# 5_ButtonsAndLeds.net
KiCad netlist of a schematic drawn in Altium Designer
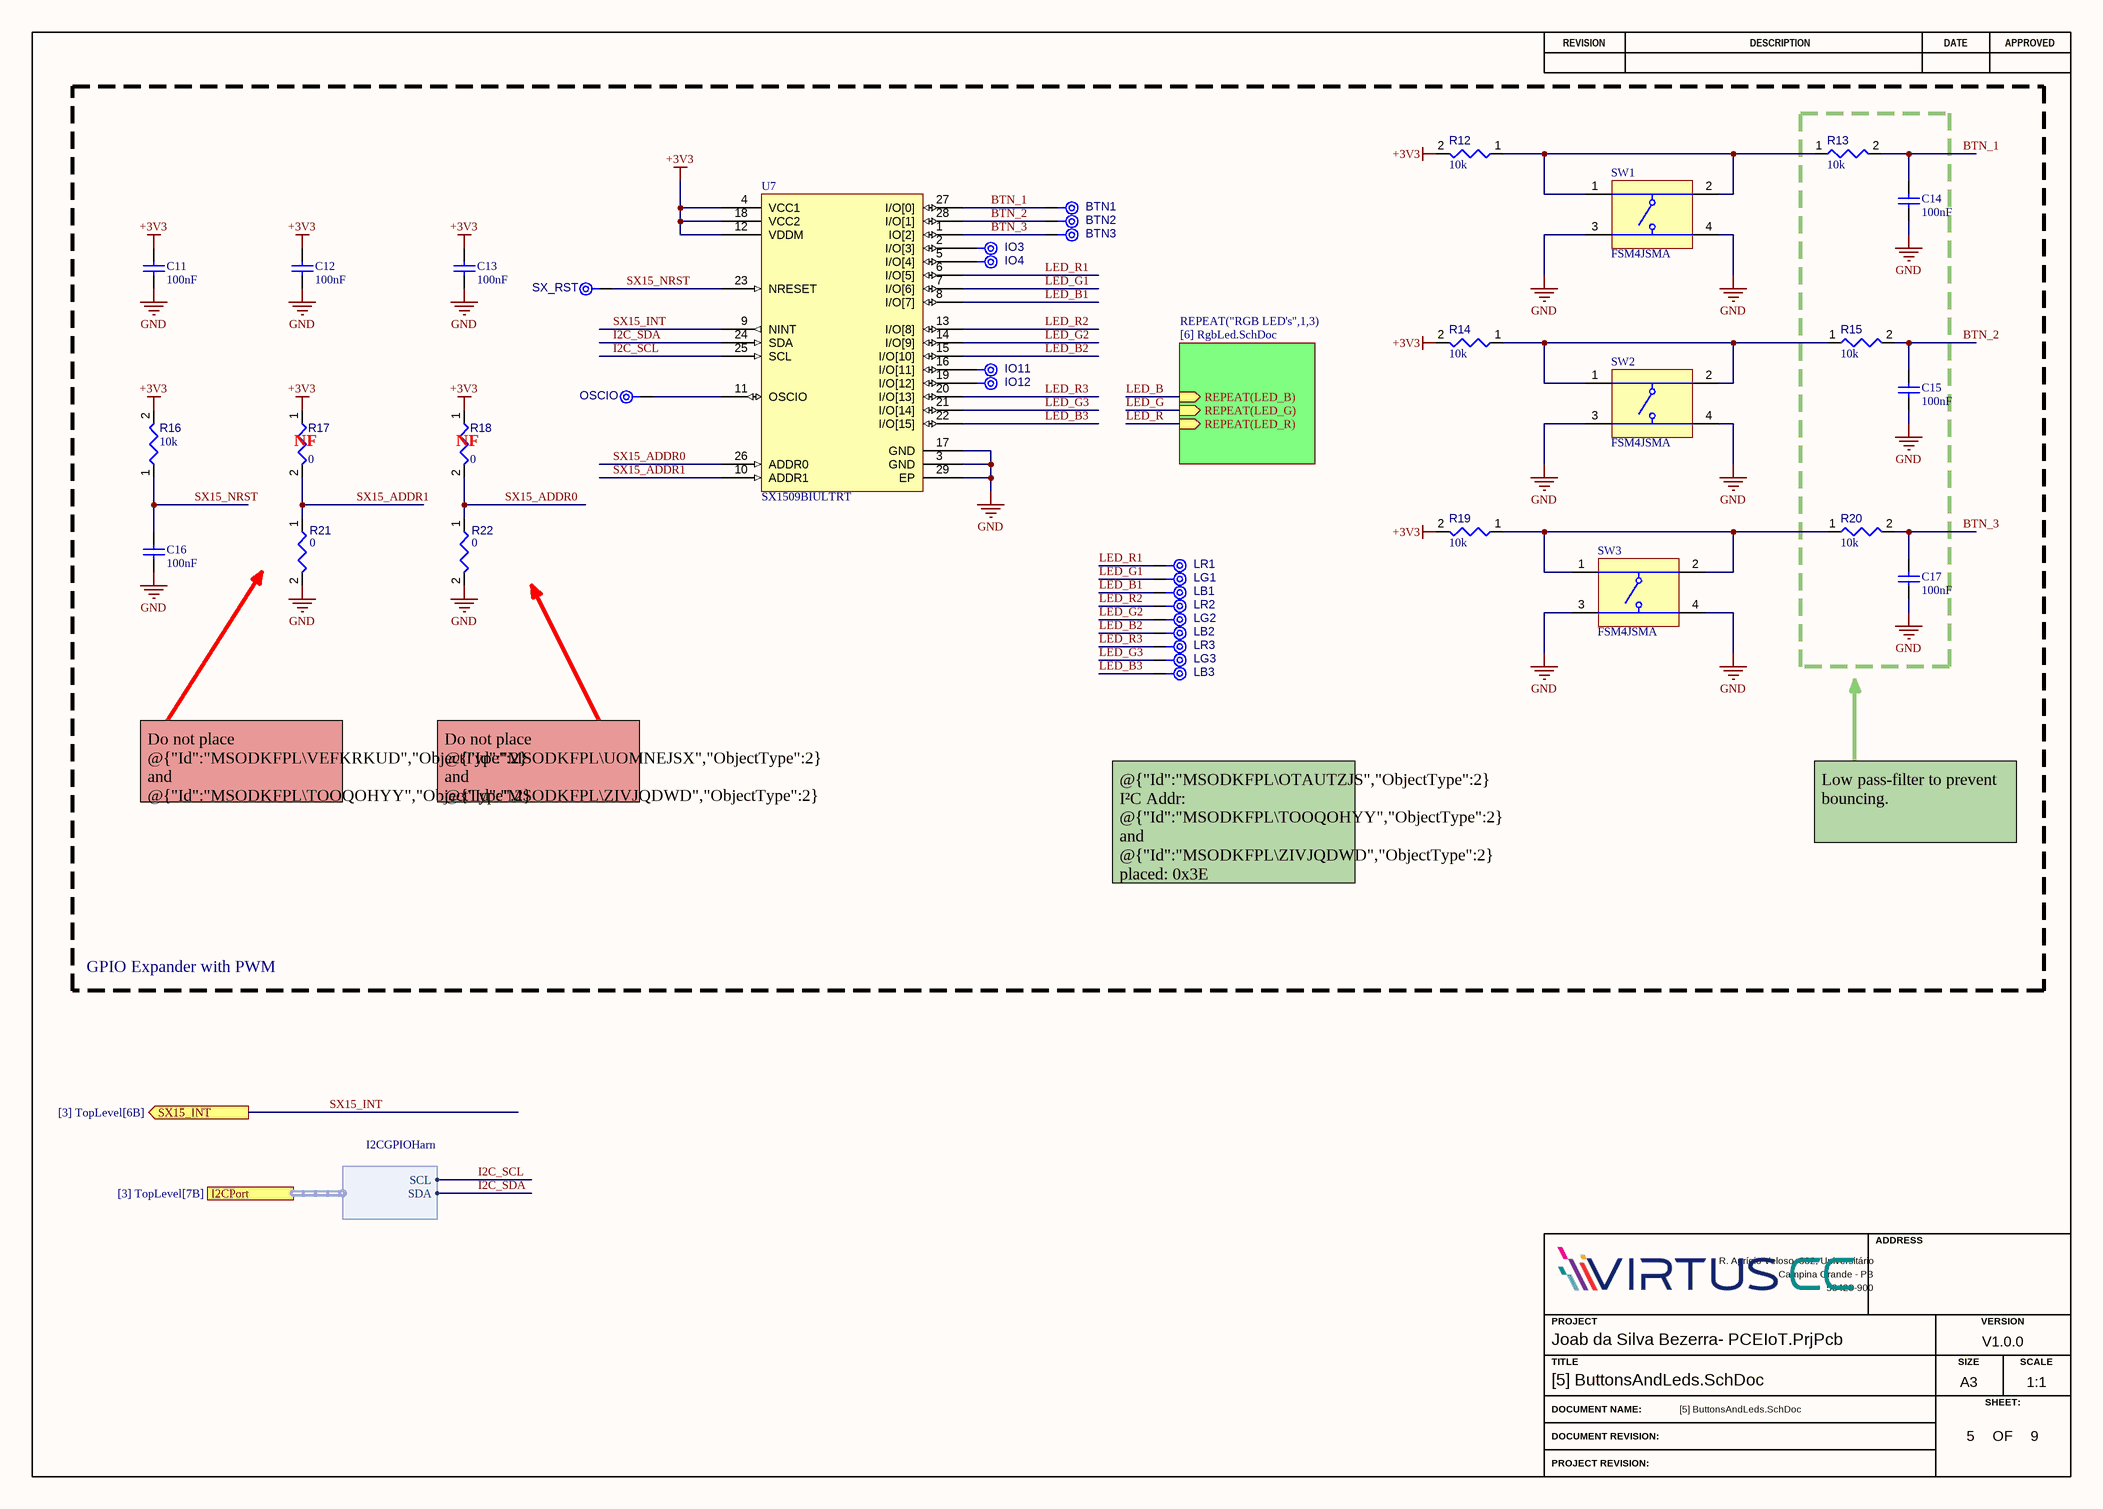
[diagram p0: [5] ButtonsAndLeds.SchDoc]

(export (version "E")
  (design (tool "Eeschema 10.0.6"))
  (components
    (comp (ref "BTN1")
      (value "TPAD6R")
      (footprint "TP06R")
      (description "0.6mm round")
      (libsource (lib "UFCG - Universidade Federal de Campina Grande") (part "CMP-001-0001-4"))
    )
    (comp (ref "BTN2")
      (value "TPAD6R")
      (footprint "TP06R")
      (description "0.6mm round")
      (libsource (lib "UFCG - Universidade Federal de Campina Grande") (part "CMP-001-0001-4"))
    )
    (comp (ref "BTN3")
      (value "TPAD6R")
      (footprint "TP06R")
      (description "0.6mm round")
      (libsource (lib "UFCG - Universidade Federal de Campina Grande") (part "CMP-001-0001-4"))
    )
    (comp (ref "C11")
      (value "100nF")
      (footprint "CAPC0603(1608)100_L")
      (description "Multilayer Ceramic Capacitor, 0.1 uF, 16 V, ± 20%, X7R, 0603 [1608 Metric]")
      (fields (field (name "TOLERANCE") "20%") (field (name "Comment") "VJ0603Y104MXJCW1BC"))
      (libsource (lib "UFCG - Universidade Federal de Campina Grande") (part "CAP"))
    )
    (comp (ref "C12")
      (value "100nF")
      (footprint "CAPC0603(1608)100_L")
      (description "Multilayer Ceramic Capacitor, 0.1 uF, 16 V, ± 20%, X7R, 0603 [1608 Metric]")
      (fields (field (name "TOLERANCE") "20%") (field (name "Comment") "VJ0603Y104MXJCW1BC"))
      (libsource (lib "UFCG - Universidade Federal de Campina Grande") (part "CAP"))
    )
    (comp (ref "C13")
      (value "100nF")
      (footprint "CAPC0603(1608)100_L")
      (description "Multilayer Ceramic Capacitor, 0.1 uF, 16 V, ± 20%, X7R, 0603 [1608 Metric]")
      (fields (field (name "TOLERANCE") "20%") (field (name "Comment") "VJ0603Y104MXJCW1BC"))
      (libsource (lib "UFCG - Universidade Federal de Campina Grande") (part "CAP"))
    )
    (comp (ref "C14")
      (value "100nF")
      (footprint "CAPC0603(1608)100_L")
      (description "Multilayer Ceramic Capacitor, 0.1 uF, 16 V, ± 20%, X7R, 0603 [1608 Metric]")
      (fields (field (name "TOLERANCE") "20%") (field (name "Comment") "VJ0603Y104MXJCW1BC"))
      (libsource (lib "UFCG - Universidade Federal de Campina Grande") (part "CAP"))
    )
    (comp (ref "C15")
      (value "100nF")
      (footprint "CAPC0603(1608)100_L")
      (description "Multilayer Ceramic Capacitor, 0.1 uF, 16 V, ± 20%, X7R, 0603 [1608 Metric]")
      (fields (field (name "TOLERANCE") "20%") (field (name "Comment") "VJ0603Y104MXJCW1BC"))
      (libsource (lib "UFCG - Universidade Federal de Campina Grande") (part "CAP"))
    )
    (comp (ref "C16")
      (value "100nF")
      (footprint "CAPC0603(1608)100_L")
      (description "Multilayer Ceramic Capacitor, 0.1 uF, 16 V, ± 20%, X7R, 0603 [1608 Metric]")
      (fields (field (name "TOLERANCE") "20%") (field (name "Comment") "VJ0603Y104MXJCW1BC"))
      (libsource (lib "UFCG - Universidade Federal de Campina Grande") (part "CAP"))
    )
    (comp (ref "C17")
      (value "100nF")
      (footprint "CAPC0603(1608)100_L")
      (description "Multilayer Ceramic Capacitor, 0.1 uF, 16 V, ± 20%, X7R, 0603 [1608 Metric]")
      (fields (field (name "TOLERANCE") "20%") (field (name "Comment") "VJ0603Y104MXJCW1BC"))
      (libsource (lib "UFCG - Universidade Federal de Campina Grande") (part "CAP"))
    )
    (comp (ref "IO3")
      (value "TPAD6R")
      (footprint "TP06R")
      (description "0.6mm round")
      (libsource (lib "UFCG - Universidade Federal de Campina Grande") (part "CMP-001-0001-4"))
    )
    (comp (ref "IO4")
      (value "TPAD6R")
      (footprint "TP06R")
      (description "0.6mm round")
      (libsource (lib "UFCG - Universidade Federal de Campina Grande") (part "CMP-001-0001-4"))
    )
    (comp (ref "IO11")
      (value "TPAD6R")
      (footprint "TP06R")
      (description "0.6mm round")
      (libsource (lib "UFCG - Universidade Federal de Campina Grande") (part "CMP-001-0001-4"))
    )
    (comp (ref "IO12")
      (value "TPAD6R")
      (footprint "TP06R")
      (description "0.6mm round")
      (libsource (lib "UFCG - Universidade Federal de Campina Grande") (part "CMP-001-0001-4"))
    )
    (comp (ref "LB1")
      (value "TPAD6R")
      (footprint "TP06R")
      (description "0.6mm round")
      (libsource (lib "UFCG - Universidade Federal de Campina Grande") (part "CMP-001-0001-4"))
    )
    (comp (ref "LB2")
      (value "TPAD6R")
      (footprint "TP06R")
      (description "0.6mm round")
      (libsource (lib "UFCG - Universidade Federal de Campina Grande") (part "CMP-001-0001-4"))
    )
    (comp (ref "LB3")
      (value "TPAD6R")
      (footprint "TP06R")
      (description "0.6mm round")
      (libsource (lib "UFCG - Universidade Federal de Campina Grande") (part "CMP-001-0001-4"))
    )
    (comp (ref "LG1")
      (value "TPAD6R")
      (footprint "TP06R")
      (description "0.6mm round")
      (libsource (lib "UFCG - Universidade Federal de Campina Grande") (part "CMP-001-0001-4"))
    )
    (comp (ref "LG2")
      (value "TPAD6R")
      (footprint "TP06R")
      (description "0.6mm round")
      (libsource (lib "UFCG - Universidade Federal de Campina Grande") (part "CMP-001-0001-4"))
    )
    (comp (ref "LG3")
      (value "TPAD6R")
      (footprint "TP06R")
      (description "0.6mm round")
      (libsource (lib "UFCG - Universidade Federal de Campina Grande") (part "CMP-001-0001-4"))
    )
    (comp (ref "LR1")
      (value "TPAD6R")
      (footprint "TP06R")
      (description "0.6mm round")
      (libsource (lib "UFCG - Universidade Federal de Campina Grande") (part "CMP-001-0001-4"))
    )
    (comp (ref "LR2")
      (value "TPAD6R")
      (footprint "TP06R")
      (description "0.6mm round")
      (libsource (lib "UFCG - Universidade Federal de Campina Grande") (part "CMP-001-0001-4"))
    )
    (comp (ref "LR3")
      (value "TPAD6R")
      (footprint "TP06R")
      (description "0.6mm round")
      (libsource (lib "UFCG - Universidade Federal de Campina Grande") (part "CMP-001-0001-4"))
    )
    (comp (ref "OSCIO")
      (value "TPAD6R")
      (footprint "TP06R")
      (description "0.6mm round")
      (libsource (lib "UFCG - Universidade Federal de Campina Grande") (part "CMP-001-0001-4"))
    )
    (comp (ref "R12")
      (value "10k")
      (footprint "RESC0603(1608)_L")
      (description "Chip Resistor, 10 KOhm, +/- 1%, 01 W, -55 to 155 degC, 0603 (1608 Metric)")
      (fields (field (name "POWER") "100mW") (field (name "TOLERANCE") "1%"))
      (libsource (lib "UFCG - Universidade Federal de Campina Grande") (part "RES-2"))
    )
    (comp (ref "R13")
      (value "10k")
      (footprint "RESC0603(1608)_L")
      (description "Chip Resistor, 10 KOhm, +/- 1%, 01 W, -55 to 155 degC, 0603 (1608 Metric)")
      (fields (field (name "POWER") "100mW") (field (name "TOLERANCE") "1%"))
      (libsource (lib "UFCG - Universidade Federal de Campina Grande") (part "RES-2"))
    )
    (comp (ref "R14")
      (value "10k")
      (footprint "RESC0603(1608)_L")
      (description "Chip Resistor, 10 KOhm, +/- 1%, 01 W, -55 to 155 degC, 0603 (1608 Metric)")
      (fields (field (name "POWER") "100mW") (field (name "TOLERANCE") "1%"))
      (libsource (lib "UFCG - Universidade Federal de Campina Grande") (part "RES-2"))
    )
    (comp (ref "R15")
      (value "10k")
      (footprint "RESC0603(1608)_L")
      (description "Chip Resistor, 10 KOhm, +/- 1%, 01 W, -55 to 155 degC, 0603 (1608 Metric)")
      (fields (field (name "POWER") "100mW") (field (name "TOLERANCE") "1%"))
      (libsource (lib "UFCG - Universidade Federal de Campina Grande") (part "RES-2"))
    )
    (comp (ref "R16")
      (value "10k")
      (footprint "RESC0603(1608)_L")
      (description "Chip Resistor, 10 KOhm, +/- 1%, 01 W, -55 to 155 degC, 0603 (1608 Metric)")
      (fields (field (name "POWER") "100mW") (field (name "TOLERANCE") "1%"))
      (libsource (lib "UFCG - Universidade Federal de Campina Grande") (part "RES-2"))
    )
    (comp (ref "R17")
      (value "0")
      (footprint "RESC0603(1608)_L")
      (description "Chip Resistor, 0 Ohm, 0.1 W, -55 to 155 degC, 0603 (1608 Metric)")
      (fields (field (name "TOLERANCE") "5%") (field (name "POWER") "100mW"))
      (libsource (lib "UFCG - Universidade Federal de Campina Grande") (part "RES-2"))
    )
    (comp (ref "R18")
      (value "0")
      (footprint "RESC0603(1608)_L")
      (description "Chip Resistor, 0 Ohm, 0.1 W, -55 to 155 degC, 0603 (1608 Metric)")
      (fields (field (name "TOLERANCE") "5%") (field (name "POWER") "100mW"))
      (libsource (lib "UFCG - Universidade Federal de Campina Grande") (part "RES-2"))
    )
    (comp (ref "R19")
      (value "10k")
      (footprint "RESC0603(1608)_L")
      (description "Chip Resistor, 10 KOhm, +/- 1%, 01 W, -55 to 155 degC, 0603 (1608 Metric)")
      (fields (field (name "POWER") "100mW") (field (name "TOLERANCE") "1%"))
      (libsource (lib "UFCG - Universidade Federal de Campina Grande") (part "RES-2"))
    )
    (comp (ref "R20")
      (value "10k")
      (footprint "RESC0603(1608)_L")
      (description "Chip Resistor, 10 KOhm, +/- 1%, 01 W, -55 to 155 degC, 0603 (1608 Metric)")
      (fields (field (name "POWER") "100mW") (field (name "TOLERANCE") "1%"))
      (libsource (lib "UFCG - Universidade Federal de Campina Grande") (part "RES-2"))
    )
    (comp (ref "R21")
      (value "0")
      (footprint "RESC0603(1608)_L")
      (description "Chip Resistor, 0 Ohm, 0.1 W, -55 to 155 degC, 0603 (1608 Metric)")
      (fields (field (name "TOLERANCE") "5%") (field (name "POWER") "100mW"))
      (libsource (lib "UFCG - Universidade Federal de Campina Grande") (part "RES-2"))
    )
    (comp (ref "R22")
      (value "0")
      (footprint "RESC0603(1608)_L")
      (description "Chip Resistor, 0 Ohm, 0.1 W, -55 to 155 degC, 0603 (1608 Metric)")
      (fields (field (name "TOLERANCE") "5%") (field (name "POWER") "100mW"))
      (libsource (lib "UFCG - Universidade Federal de Campina Grande") (part "RES-2"))
    )
    (comp (ref "SW1")
      (value "FSM4JSMA")
      (footprint "TECO-FSM4JSMA_V")
      (description "Switch Tactile OFF (ON) SPST Round Button Gull Wing 0.05A 12VDC 1.57N SMD Loose Piece")
      (libsource (lib "UFCG - Universidade Federal de Campina Grande") (part "SW-SPST-4_A"))
    )
    (comp (ref "SW2")
      (value "FSM4JSMA")
      (footprint "TECO-FSM4JSMA_V")
      (description "Switch Tactile OFF (ON) SPST Round Button Gull Wing 0.05A 12VDC 1.57N SMD Loose Piece")
      (libsource (lib "UFCG - Universidade Federal de Campina Grande") (part "SW-SPST-4_A"))
    )
    (comp (ref "SW3")
      (value "FSM4JSMA")
      (footprint "TECO-FSM4JSMA_V")
      (description "Switch Tactile OFF (ON) SPST Round Button Gull Wing 0.05A 12VDC 1.57N SMD Loose Piece")
      (libsource (lib "UFCG - Universidade Federal de Campina Grande") (part "SW-SPST-4_A"))
    )
    (comp (ref "SX_RST")
      (value "TPAD6R")
      (footprint "TP06R")
      (description "0.6mm round")
      (libsource (lib "UFCG - Universidade Federal de Campina Grande") (part "CMP-001-0001-4"))
    )
    (comp (ref "U7")
      (value "SX1509BIULTRT")
      (footprint "QFN40P410X410X60_HS-29N")
      (description "IC Gpio Expander I2C 16CH 28QFN / I2C Interface 5.5V 28-PIN Qfn-ut Ep T/r")
      (libsource (lib "UFCG - Universidade Federal de Campina Grande") (part "New symbol 1"))
    )
  )
  (nets
    (net (code "2") (name "+3V3") (class "Default")
      (node (ref "C11") (pin "2") (pinfunction "2_2") (pintype "passive"))
      (node (ref "C12") (pin "2") (pinfunction "2_2") (pintype "passive"))
      (node (ref "C13") (pin "2") (pinfunction "2_2") (pintype "passive"))
      (node (ref "R12") (pin "2") (pinfunction "2_2") (pintype "passive"))
      (node (ref "R14") (pin "2") (pinfunction "2_2") (pintype "passive"))
      (node (ref "R16") (pin "2") (pinfunction "2_2") (pintype "passive"))
      (node (ref "R17") (pin "1") (pinfunction "1_1") (pintype "passive"))
      (node (ref "R18") (pin "1") (pinfunction "1_1") (pintype "passive"))
      (node (ref "R19") (pin "2") (pinfunction "2_2") (pintype "passive"))
      (node (ref "U7") (pin "12") (pinfunction "VDDM_12") (pintype "power_in"))
      (node (ref "U7") (pin "18") (pinfunction "VCC2_18") (pintype "power_in"))
      (node (ref "U7") (pin "4") (pinfunction "VCC1_4") (pintype "power_in"))
    )
    (net (code "3") (name "/BTN_1") (class "Default")
      (node (ref "BTN1") (pin "1") (pinfunction "TP_1") (pintype "passive"))
      (node (ref "C14") (pin "2") (pinfunction "2_2") (pintype "passive"))
      (node (ref "R13") (pin "2") (pinfunction "2_2") (pintype "passive"))
      (node (ref "U7") (pin "27") (pinfunction "I/O[0]_27") (pintype "bidirectional"))
    )
    (net (code "4") (name "/BTN_2") (class "Default")
      (node (ref "BTN2") (pin "1") (pinfunction "TP_1") (pintype "passive"))
      (node (ref "C15") (pin "2") (pinfunction "2_2") (pintype "passive"))
      (node (ref "R15") (pin "2") (pinfunction "2_2") (pintype "passive"))
      (node (ref "U7") (pin "28") (pinfunction "I/O[1]_28") (pintype "bidirectional"))
    )
    (net (code "5") (name "/BTN_3") (class "Default")
      (node (ref "BTN3") (pin "1") (pinfunction "TP_1") (pintype "passive"))
      (node (ref "C17") (pin "2") (pinfunction "2_2") (pintype "passive"))
      (node (ref "R20") (pin "2") (pinfunction "2_2") (pintype "passive"))
      (node (ref "U7") (pin "1") (pinfunction "IO[2]_1") (pintype "bidirectional"))
    )
    (net (code "6") (name "/I2C_SCL") (class "Default")
      (node (ref "U7") (pin "25") (pinfunction "SCL_25") (pintype "input"))
    )
    (net (code "7") (name "/I2C_SDA") (class "Default")
      (node (ref "U7") (pin "24") (pinfunction "SDA_24") (pintype "input"))
    )
    (net (code "9") (name "/LED_B1") (class "Default")
      (node (ref "LB1") (pin "1") (pinfunction "TP_1") (pintype "passive"))
      (node (ref "U7") (pin "8") (pinfunction "I/O[7]_8") (pintype "bidirectional"))
    )
    (net (code "10") (name "/LED_B2") (class "Default")
      (node (ref "LB2") (pin "1") (pinfunction "TP_1") (pintype "passive"))
      (node (ref "U7") (pin "15") (pinfunction "I/O[10]_15") (pintype "bidirectional"))
    )
    (net (code "11") (name "/LED_B3") (class "Default")
      (node (ref "LB3") (pin "1") (pinfunction "TP_1") (pintype "passive"))
      (node (ref "U7") (pin "22") (pinfunction "I/O[15]_22") (pintype "bidirectional"))
    )
    (net (code "13") (name "/LED_G1") (class "Default")
      (node (ref "LG1") (pin "1") (pinfunction "TP_1") (pintype "passive"))
      (node (ref "U7") (pin "7") (pinfunction "I/O[6]_7") (pintype "bidirectional"))
    )
    (net (code "14") (name "/LED_G2") (class "Default")
      (node (ref "LG2") (pin "1") (pinfunction "TP_1") (pintype "passive"))
      (node (ref "U7") (pin "14") (pinfunction "I/O[9]_14") (pintype "bidirectional"))
    )
    (net (code "15") (name "/LED_G3") (class "Default")
      (node (ref "LG3") (pin "1") (pinfunction "TP_1") (pintype "passive"))
      (node (ref "U7") (pin "21") (pinfunction "I/O[14]_21") (pintype "bidirectional"))
    )
    (net (code "17") (name "/LED_R1") (class "Default")
      (node (ref "LR1") (pin "1") (pinfunction "TP_1") (pintype "passive"))
      (node (ref "U7") (pin "6") (pinfunction "I/O[5]_6") (pintype "bidirectional"))
    )
    (net (code "18") (name "/LED_R2") (class "Default")
      (node (ref "LR2") (pin "1") (pinfunction "TP_1") (pintype "passive"))
      (node (ref "U7") (pin "13") (pinfunction "I/O[8]_13") (pintype "bidirectional"))
    )
    (net (code "19") (name "/LED_R3") (class "Default")
      (node (ref "LR3") (pin "1") (pinfunction "TP_1") (pintype "passive"))
      (node (ref "U7") (pin "20") (pinfunction "I/O[13]_20") (pintype "bidirectional"))
    )
    (net (code "20") (name "/SX15_ADDR0") (class "Default")
      (node (ref "R18") (pin "2") (pinfunction "2_2") (pintype "passive"))
      (node (ref "R22") (pin "1") (pinfunction "1_1") (pintype "passive"))
      (node (ref "U7") (pin "26") (pinfunction "ADDR0_26") (pintype "input"))
    )
    (net (code "21") (name "/SX15_ADDR1") (class "Default")
      (node (ref "R17") (pin "2") (pinfunction "2_2") (pintype "passive"))
      (node (ref "R21") (pin "1") (pinfunction "1_1") (pintype "passive"))
      (node (ref "U7") (pin "10") (pinfunction "ADDR1_10") (pintype "input"))
    )
    (net (code "22") (name "/SX15_INT") (class "Default")
      (node (ref "U7") (pin "9") (pinfunction "NINT_9") (pintype "output"))
    )
    (net (code "23") (name "/SX15_NRST") (class "Default")
      (node (ref "C16") (pin "2") (pinfunction "2_2") (pintype "passive"))
      (node (ref "R16") (pin "1") (pinfunction "1_1") (pintype "passive"))
      (node (ref "SX_RST") (pin "1") (pinfunction "TP_1") (pintype "passive"))
      (node (ref "U7") (pin "23") (pinfunction "NRESET_23") (pintype "input"))
    )
    (net (code "25") (name "GND") (class "Default")
      (node (ref "C11") (pin "1") (pinfunction "1_1") (pintype "passive"))
      (node (ref "C12") (pin "1") (pinfunction "1_1") (pintype "passive"))
      (node (ref "C13") (pin "1") (pinfunction "1_1") (pintype "passive"))
      (node (ref "C14") (pin "1") (pinfunction "1_1") (pintype "passive"))
      (node (ref "C15") (pin "1") (pinfunction "1_1") (pintype "passive"))
      (node (ref "C16") (pin "1") (pinfunction "1_1") (pintype "passive"))
      (node (ref "C17") (pin "1") (pinfunction "1_1") (pintype "passive"))
      (node (ref "R21") (pin "2") (pinfunction "2_2") (pintype "passive"))
      (node (ref "R22") (pin "2") (pinfunction "2_2") (pintype "passive"))
      (node (ref "SW1") (pin "3") (pinfunction "3_3") (pintype "passive"))
      (node (ref "SW1") (pin "4") (pinfunction "4_4") (pintype "passive"))
      (node (ref "SW2") (pin "3") (pinfunction "3_3") (pintype "passive"))
      (node (ref "SW2") (pin "4") (pinfunction "4_4") (pintype "passive"))
      (node (ref "SW3") (pin "3") (pinfunction "3_3") (pintype "passive"))
      (node (ref "SW3") (pin "4") (pinfunction "4_4") (pintype "passive"))
      (node (ref "U7") (pin "17") (pinfunction "GND_17") (pintype "power_in"))
      (node (ref "U7") (pin "29") (pinfunction "EP_29") (pintype "power_in"))
      (node (ref "U7") (pin "3") (pinfunction "GND_3") (pintype "power_in"))
    )
    (net (code "26") (name "Net-(IO3-TP)") (class "Default")
      (node (ref "IO3") (pin "1") (pinfunction "TP_1") (pintype "passive"))
      (node (ref "U7") (pin "2") (pinfunction "I/O[3]_2") (pintype "bidirectional"))
    )
    (net (code "27") (name "Net-(IO4-TP)") (class "Default")
      (node (ref "IO4") (pin "1") (pinfunction "TP_1") (pintype "passive"))
      (node (ref "U7") (pin "5") (pinfunction "I/O[4]_5") (pintype "bidirectional"))
    )
    (net (code "28") (name "Net-(IO11-TP)") (class "Default")
      (node (ref "IO11") (pin "1") (pinfunction "TP_1") (pintype "passive"))
      (node (ref "U7") (pin "16") (pinfunction "I/O[11]_16") (pintype "bidirectional"))
    )
    (net (code "29") (name "Net-(IO12-TP)") (class "Default")
      (node (ref "IO12") (pin "1") (pinfunction "TP_1") (pintype "passive"))
      (node (ref "U7") (pin "19") (pinfunction "I/O[12]_19") (pintype "bidirectional"))
    )
    (net (code "30") (name "Net-(OSCIO-TP)") (class "Default")
      (node (ref "OSCIO") (pin "1") (pinfunction "TP_1") (pintype "passive"))
      (node (ref "U7") (pin "11") (pinfunction "OSCIO_11") (pintype "bidirectional"))
    )
    (net (code "31") (name "Net-(R12-Pad1)") (class "Default")
      (node (ref "R12") (pin "1") (pinfunction "1_1") (pintype "passive"))
      (node (ref "R13") (pin "1") (pinfunction "1_1") (pintype "passive"))
      (node (ref "SW1") (pin "1") (pinfunction "1_1") (pintype "passive"))
      (node (ref "SW1") (pin "2") (pinfunction "2_2") (pintype "passive"))
    )
    (net (code "32") (name "Net-(R14-Pad1)") (class "Default")
      (node (ref "R14") (pin "1") (pinfunction "1_1") (pintype "passive"))
      (node (ref "R15") (pin "1") (pinfunction "1_1") (pintype "passive"))
      (node (ref "SW2") (pin "1") (pinfunction "1_1") (pintype "passive"))
      (node (ref "SW2") (pin "2") (pinfunction "2_2") (pintype "passive"))
    )
    (net (code "33") (name "Net-(R19-Pad1)") (class "Default")
      (node (ref "R19") (pin "1") (pinfunction "1_1") (pintype "passive"))
      (node (ref "R20") (pin "1") (pinfunction "1_1") (pintype "passive"))
      (node (ref "SW3") (pin "1") (pinfunction "1_1") (pintype "passive"))
      (node (ref "SW3") (pin "2") (pinfunction "2_2") (pintype "passive"))
    )
  )
)
